# controller2.net
KiCad netlist of a schematic drawn in EAGLE
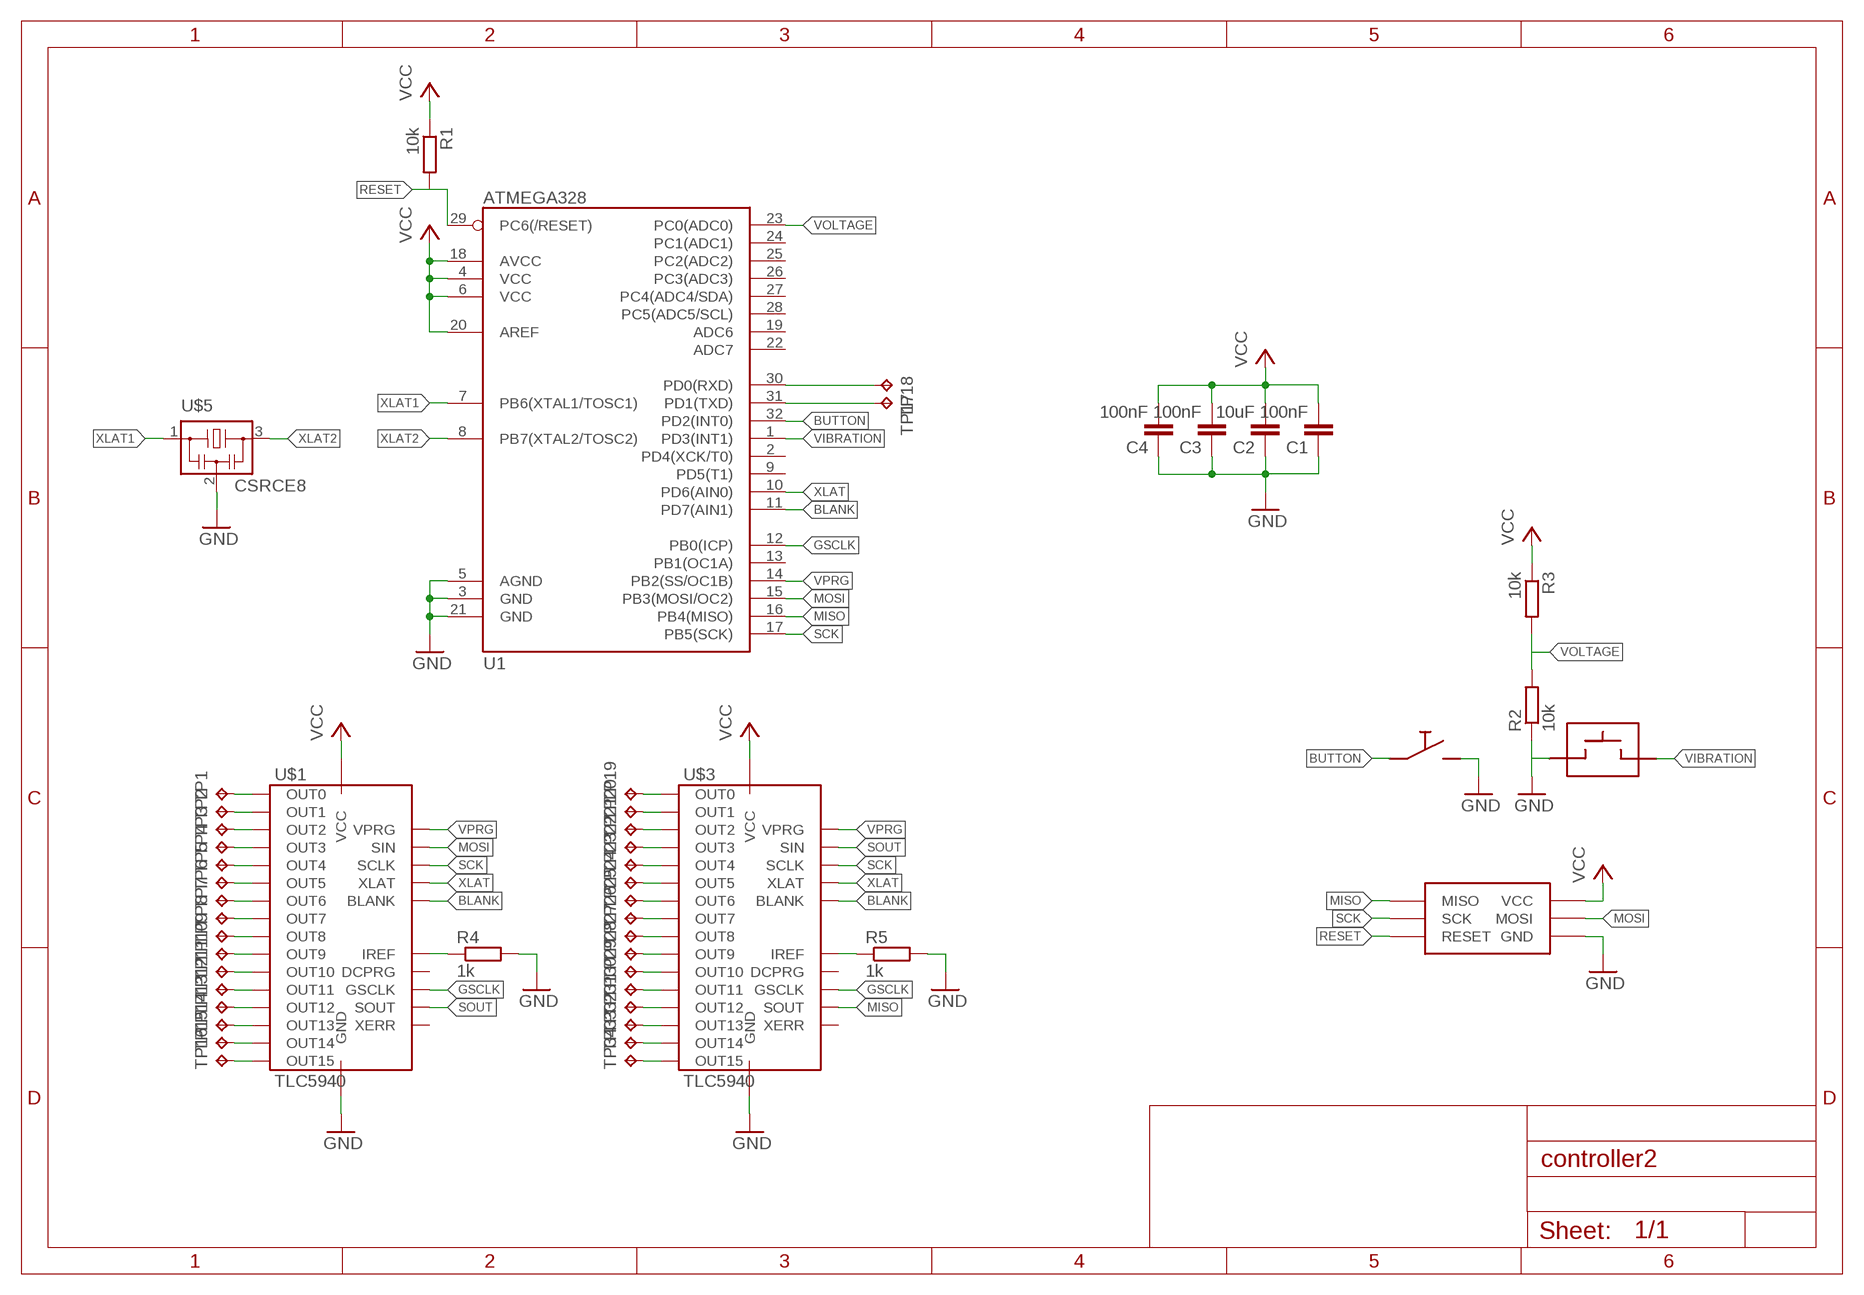
[diagram p0: schematic, sheet 1]

(export (version "E")
  (design (tool "Eeschema 10.0.6"))
  (components
    (comp (ref "C1")
      (value "100nF")
      (footprint "eagle-import:C0603")
      (libsource (lib "eagle-import") (part "C-EUC0603"))
    )
    (comp (ref "C2")
      (value "10uF")
      (footprint "eagle-import:C0805")
      (libsource (lib "eagle-import") (part "C-EUC0805"))
    )
    (comp (ref "C3")
      (value "100nF")
      (footprint "eagle-import:C0603")
      (libsource (lib "eagle-import") (part "C-EUC0603"))
    )
    (comp (ref "C4")
      (value "100nF")
      (footprint "eagle-import:C0603")
      (libsource (lib "eagle-import") (part "C-EUC0603"))
    )
    (comp (ref "R1")
      (value "10k")
      (footprint "eagle-import:R0603")
      (libsource (lib "eagle-import") (part "R-EU_R0603"))
    )
    (comp (ref "R2")
      (value "10k")
      (footprint "eagle-import:R0603")
      (libsource (lib "eagle-import") (part "R-EU_R0603"))
    )
    (comp (ref "R3")
      (value "10k")
      (footprint "eagle-import:R0603")
      (libsource (lib "eagle-import") (part "R-EU_R0603"))
    )
    (comp (ref "R4")
      (value "1k")
      (footprint "eagle-import:R0603")
      (libsource (lib "eagle-import") (part "R-EU_R0603"))
    )
    (comp (ref "R5")
      (value "1k")
      (footprint "eagle-import:R0603")
      (libsource (lib "eagle-import") (part "R-EU_R0603"))
    )
    (comp (ref "TP1")
      (value "TPTP15SQ")
      (footprint "eagle-import:TP15SQ")
      (libsource (lib "eagle-import") (part "TPTP15SQ"))
    )
    (comp (ref "TP2")
      (value "TPTP15SQ")
      (footprint "eagle-import:TP15SQ")
      (libsource (lib "eagle-import") (part "TPTP15SQ"))
    )
    (comp (ref "TP3")
      (value "TPTP15SQ")
      (footprint "eagle-import:TP15SQ")
      (libsource (lib "eagle-import") (part "TPTP15SQ"))
    )
    (comp (ref "TP4")
      (value "TPTP15SQ")
      (footprint "eagle-import:TP15SQ")
      (libsource (lib "eagle-import") (part "TPTP15SQ"))
    )
    (comp (ref "TP5")
      (value "TPTP15SQ")
      (footprint "eagle-import:TP15SQ")
      (libsource (lib "eagle-import") (part "TPTP15SQ"))
    )
    (comp (ref "TP6")
      (value "TPTP15SQ")
      (footprint "eagle-import:TP15SQ")
      (libsource (lib "eagle-import") (part "TPTP15SQ"))
    )
    (comp (ref "TP7")
      (value "TPTP15SQ")
      (footprint "eagle-import:TP15SQ")
      (libsource (lib "eagle-import") (part "TPTP15SQ"))
    )
    (comp (ref "TP8")
      (value "TPTP15SQ")
      (footprint "eagle-import:TP15SQ")
      (libsource (lib "eagle-import") (part "TPTP15SQ"))
    )
    (comp (ref "TP9")
      (value "TPTP15SQ")
      (footprint "eagle-import:TP15SQ")
      (libsource (lib "eagle-import") (part "TPTP15SQ"))
    )
    (comp (ref "TP10")
      (value "TPTP15SQ")
      (footprint "eagle-import:TP15SQ")
      (libsource (lib "eagle-import") (part "TPTP15SQ"))
    )
    (comp (ref "TP11")
      (value "TPTP15SQ")
      (footprint "eagle-import:TP15SQ")
      (libsource (lib "eagle-import") (part "TPTP15SQ"))
    )
    (comp (ref "TP12")
      (value "TPTP15SQ")
      (footprint "eagle-import:TP15SQ")
      (libsource (lib "eagle-import") (part "TPTP15SQ"))
    )
    (comp (ref "TP13")
      (value "TPTP15SQ")
      (footprint "eagle-import:TP15SQ")
      (libsource (lib "eagle-import") (part "TPTP15SQ"))
    )
    (comp (ref "TP14")
      (value "TPTP15SQ")
      (footprint "eagle-import:TP15SQ")
      (libsource (lib "eagle-import") (part "TPTP15SQ"))
    )
    (comp (ref "TP15")
      (value "TPTP15SQ")
      (footprint "eagle-import:TP15SQ")
      (libsource (lib "eagle-import") (part "TPTP15SQ"))
    )
    (comp (ref "TP16")
      (value "TPTP15SQ")
      (footprint "eagle-import:TP15SQ")
      (libsource (lib "eagle-import") (part "TPTP15SQ"))
    )
    (comp (ref "TP17")
      (value "TPTP15SQ")
      (footprint "eagle-import:TP15SQ")
      (libsource (lib "eagle-import") (part "TPTP15SQ"))
    )
    (comp (ref "TP18")
      (value "TPTP15SQ")
      (footprint "eagle-import:TP15SQ")
      (libsource (lib "eagle-import") (part "TPTP15SQ"))
    )
    (comp (ref "TP19")
      (value "TPTP15SQ")
      (footprint "eagle-import:TP15SQ")
      (libsource (lib "eagle-import") (part "TPTP15SQ"))
    )
    (comp (ref "TP20")
      (value "TPTP15SQ")
      (footprint "eagle-import:TP15SQ")
      (libsource (lib "eagle-import") (part "TPTP15SQ"))
    )
    (comp (ref "TP21")
      (value "TPTP15SQ")
      (footprint "eagle-import:TP15SQ")
      (libsource (lib "eagle-import") (part "TPTP15SQ"))
    )
    (comp (ref "TP22")
      (value "TPTP15SQ")
      (footprint "eagle-import:TP15SQ")
      (libsource (lib "eagle-import") (part "TPTP15SQ"))
    )
    (comp (ref "TP23")
      (value "TPTP15SQ")
      (footprint "eagle-import:TP15SQ")
      (libsource (lib "eagle-import") (part "TPTP15SQ"))
    )
    (comp (ref "TP24")
      (value "TPTP15SQ")
      (footprint "eagle-import:TP15SQ")
      (libsource (lib "eagle-import") (part "TPTP15SQ"))
    )
    (comp (ref "TP25")
      (value "TPTP15SQ")
      (footprint "eagle-import:TP15SQ")
      (libsource (lib "eagle-import") (part "TPTP15SQ"))
    )
    (comp (ref "TP26")
      (value "TPTP15SQ")
      (footprint "eagle-import:TP15SQ")
      (libsource (lib "eagle-import") (part "TPTP15SQ"))
    )
    (comp (ref "TP27")
      (value "TPTP15SQ")
      (footprint "eagle-import:TP15SQ")
      (libsource (lib "eagle-import") (part "TPTP15SQ"))
    )
    (comp (ref "TP28")
      (value "TPTP15SQ")
      (footprint "eagle-import:TP15SQ")
      (libsource (lib "eagle-import") (part "TPTP15SQ"))
    )
    (comp (ref "TP29")
      (value "TPTP15SQ")
      (footprint "eagle-import:TP15SQ")
      (libsource (lib "eagle-import") (part "TPTP15SQ"))
    )
    (comp (ref "TP30")
      (value "TPTP15SQ")
      (footprint "eagle-import:TP15SQ")
      (libsource (lib "eagle-import") (part "TPTP15SQ"))
    )
    (comp (ref "TP31")
      (value "TPTP15SQ")
      (footprint "eagle-import:TP15SQ")
      (libsource (lib "eagle-import") (part "TPTP15SQ"))
    )
    (comp (ref "TP32")
      (value "TPTP15SQ")
      (footprint "eagle-import:TP15SQ")
      (libsource (lib "eagle-import") (part "TPTP15SQ"))
    )
    (comp (ref "TP33")
      (value "TPTP15SQ")
      (footprint "eagle-import:TP15SQ")
      (libsource (lib "eagle-import") (part "TPTP15SQ"))
    )
    (comp (ref "TP34")
      (value "TPTP15SQ")
      (footprint "eagle-import:TP15SQ")
      (libsource (lib "eagle-import") (part "TPTP15SQ"))
    )
    (comp (ref "U$1")
      (value "TLC5940")
      (footprint "eagle-import:PWP_28PIN")
      (libsource (lib "eagle-import") (part "TLC5940"))
    )
    (comp (ref "U$2")
      (value "ISP_SPECIALS")
      (footprint "eagle-import:ISP_RM2_00_STRAIGHT")
      (libsource (lib "eagle-import") (part "ISP_SPECIALS"))
    )
    (comp (ref "U$3")
      (value "TLC5940")
      (footprint "eagle-import:PWP_28PIN")
      (libsource (lib "eagle-import") (part "TLC5940"))
    )
    (comp (ref "U$4")
      (value "MOTION_SENSOR")
      (footprint "eagle-import:MOTION")
      (libsource (lib "eagle-import") (part "MOTION_SENSOR"))
    )
    (comp (ref "U$5")
      (value "CSRCE8")
      (footprint "eagle-import:CSTCE_G")
      (libsource (lib "eagle-import") (part "CSRCE8"))
    )
    (comp (ref "U$6")
      (value "SWITCH")
      (footprint "eagle-import:EVQPSG02K")
      (libsource (lib "eagle-import") (part "SWITCH"))
    )
    (comp (ref "U1")
      (value "ATMEGA328")
      (footprint "eagle-import:TQFP32-08")
      (libsource (lib "eagle-import") (part "ATMEGA328"))
    )
  )
  (nets
    (net (code "1") (name "BLANK") (class "Default")
      (node (ref "U$1") (pin "P2") (pinfunction "BLANK_P2") (pintype "input"))
      (node (ref "U$3") (pin "P2") (pinfunction "BLANK_P2") (pintype "input"))
      (node (ref "U1") (pin "11") (pinfunction "PD7(AIN1)_11") (pintype "bidirectional"))
    )
    (net (code "2") (name "BUTTON") (class "Default")
      (node (ref "U$6") (pin "A") (pinfunction "P$1_A") (pintype "bidirectional"))
      (node (ref "U$6") (pin "A@2") (pinfunction "P$1_A@2") (pintype "bidirectional"))
      (node (ref "U1") (pin "32") (pinfunction "PD2(INT0)_32") (pintype "bidirectional"))
    )
    (net (code "3") (name "GND") (class "Default")
      (node (ref "C1") (pin "1") (pinfunction "1_1") (pintype "passive"))
      (node (ref "C2") (pin "1") (pinfunction "1_1") (pintype "passive"))
      (node (ref "C3") (pin "1") (pinfunction "1_1") (pintype "passive"))
      (node (ref "C4") (pin "1") (pinfunction "1_1") (pintype "passive"))
      (node (ref "R2") (pin "1") (pinfunction "1_1") (pintype "passive"))
      (node (ref "R4") (pin "2") (pinfunction "2_2") (pintype "passive"))
      (node (ref "R5") (pin "2") (pinfunction "2_2") (pintype "passive"))
      (node (ref "U$1") (pin "P1") (pinfunction "GND_P1") (pintype "power_in"))
      (node (ref "U$1") (pin "P29") (pinfunction "GND_P29") (pintype "power_in"))
      (node (ref "U$2") (pin "VCC") (pinfunction "GND_VCC") (pintype "bidirectional"))
      (node (ref "U$3") (pin "P1") (pinfunction "GND_P1") (pintype "power_in"))
      (node (ref "U$3") (pin "P29") (pinfunction "GND_P29") (pintype "power_in"))
      (node (ref "U$4") (pin "P$1") (pinfunction "IN_P$1") (pintype "bidirectional"))
      (node (ref "U$5") (pin "2") (pinfunction "2_2") (pintype "passive"))
      (node (ref "U$6") (pin "B") (pinfunction "P$2_B") (pintype "bidirectional"))
      (node (ref "U$6") (pin "B@2") (pinfunction "P$2_B@2") (pintype "bidirectional"))
      (node (ref "U1") (pin "21") (pinfunction "GND_21") (pintype "bidirectional"))
      (node (ref "U1") (pin "3") (pinfunction "GND_3") (pintype "bidirectional"))
      (node (ref "U1") (pin "5") (pinfunction "AGND_5") (pintype "bidirectional"))
    )
    (net (code "4") (name "GSCLK") (class "Default")
      (node (ref "U$1") (pin "P25") (pinfunction "GSCLK_P25") (pintype "input"))
      (node (ref "U$3") (pin "P25") (pinfunction "GSCLK_P25") (pintype "input"))
      (node (ref "U1") (pin "12") (pinfunction "PB0(ICP)_12") (pintype "bidirectional"))
    )
    (net (code "5") (name "MISO") (class "Default")
      (node (ref "U$2") (pin "RESET") (pinfunction "MISO_RESET") (pintype "bidirectional"))
      (node (ref "U$3") (pin "P24") (pinfunction "SOUT_P24") (pintype "output"))
      (node (ref "U1") (pin "16") (pinfunction "PB4(MISO)_16") (pintype "bidirectional"))
    )
    (net (code "6") (name "MOSI") (class "Default")
      (node (ref "U$1") (pin "P5") (pinfunction "SIN_P5") (pintype "input"))
      (node (ref "U$2") (pin "MOSI") (pinfunction "MOSI_MOSI") (pintype "bidirectional"))
      (node (ref "U1") (pin "15") (pinfunction "PB3(MOSI/OC2)_15") (pintype "bidirectional"))
    )
    (net (code "7") (name "Net-(U$1-IREF)") (class "Default")
      (node (ref "R4") (pin "1") (pinfunction "1_1") (pintype "passive"))
      (node (ref "U$1") (pin "P27") (pinfunction "IREF_P27") (pintype "passive"))
    )
    (net (code "8") (name "Net-(U$1-OUT0)") (class "Default")
      (node (ref "TP1") (pin "TP") (pinfunction "TP_TP") (pintype "input"))
      (node (ref "U$1") (pin "P7") (pinfunction "OUT0_P7") (pintype "open_collector"))
    )
    (net (code "9") (name "Net-(U$1-OUT1)") (class "Default")
      (node (ref "TP2") (pin "TP") (pinfunction "TP_TP") (pintype "input"))
      (node (ref "U$1") (pin "P8") (pinfunction "OUT1_P8") (pintype "open_collector"))
    )
    (net (code "10") (name "Net-(U$1-OUT2)") (class "Default")
      (node (ref "TP3") (pin "TP") (pinfunction "TP_TP") (pintype "input"))
      (node (ref "U$1") (pin "P9") (pinfunction "OUT2_P9") (pintype "open_collector"))
    )
    (net (code "11") (name "Net-(U$1-OUT3)") (class "Default")
      (node (ref "TP4") (pin "TP") (pinfunction "TP_TP") (pintype "input"))
      (node (ref "U$1") (pin "P10") (pinfunction "OUT3_P10") (pintype "open_collector"))
    )
    (net (code "12") (name "Net-(U$1-OUT4)") (class "Default")
      (node (ref "TP5") (pin "TP") (pinfunction "TP_TP") (pintype "input"))
      (node (ref "U$1") (pin "P11") (pinfunction "OUT4_P11") (pintype "open_collector"))
    )
    (net (code "13") (name "Net-(U$1-OUT5)") (class "Default")
      (node (ref "TP6") (pin "TP") (pinfunction "TP_TP") (pintype "input"))
      (node (ref "U$1") (pin "P12") (pinfunction "OUT5_P12") (pintype "open_collector"))
    )
    (net (code "14") (name "Net-(U$1-OUT6)") (class "Default")
      (node (ref "TP7") (pin "TP") (pinfunction "TP_TP") (pintype "input"))
      (node (ref "U$1") (pin "P13") (pinfunction "OUT6_P13") (pintype "open_collector"))
    )
    (net (code "15") (name "Net-(U$1-OUT7)") (class "Default")
      (node (ref "TP8") (pin "TP") (pinfunction "TP_TP") (pintype "input"))
      (node (ref "U$1") (pin "P14") (pinfunction "OUT7_P14") (pintype "open_collector"))
    )
    (net (code "16") (name "Net-(U$1-OUT8)") (class "Default")
      (node (ref "TP9") (pin "TP") (pinfunction "TP_TP") (pintype "input"))
      (node (ref "U$1") (pin "P15") (pinfunction "OUT8_P15") (pintype "open_collector"))
    )
    (net (code "17") (name "Net-(U$1-OUT9)") (class "Default")
      (node (ref "TP10") (pin "TP") (pinfunction "TP_TP") (pintype "input"))
      (node (ref "U$1") (pin "P16") (pinfunction "OUT9_P16") (pintype "open_collector"))
    )
    (net (code "18") (name "Net-(U$1-OUT10)") (class "Default")
      (node (ref "TP11") (pin "TP") (pinfunction "TP_TP") (pintype "input"))
      (node (ref "U$1") (pin "P17") (pinfunction "OUT10_P17") (pintype "open_collector"))
    )
    (net (code "19") (name "Net-(U$1-OUT11)") (class "Default")
      (node (ref "TP12") (pin "TP") (pinfunction "TP_TP") (pintype "input"))
      (node (ref "U$1") (pin "P18") (pinfunction "OUT11_P18") (pintype "open_collector"))
    )
    (net (code "20") (name "Net-(U$1-OUT12)") (class "Default")
      (node (ref "TP13") (pin "TP") (pinfunction "TP_TP") (pintype "input"))
      (node (ref "U$1") (pin "P19") (pinfunction "OUT12_P19") (pintype "open_collector"))
    )
    (net (code "21") (name "Net-(U$1-OUT13)") (class "Default")
      (node (ref "TP14") (pin "TP") (pinfunction "TP_TP") (pintype "input"))
      (node (ref "U$1") (pin "P20") (pinfunction "OUT13_P20") (pintype "open_collector"))
    )
    (net (code "22") (name "Net-(U$1-OUT14)") (class "Default")
      (node (ref "TP15") (pin "TP") (pinfunction "TP_TP") (pintype "input"))
      (node (ref "U$1") (pin "P21") (pinfunction "OUT14_P21") (pintype "open_collector"))
    )
    (net (code "23") (name "Net-(U$1-OUT15)") (class "Default")
      (node (ref "TP16") (pin "TP") (pinfunction "TP_TP") (pintype "input"))
      (node (ref "U$1") (pin "P22") (pinfunction "OUT15_P22") (pintype "open_collector"))
    )
    (net (code "24") (name "Net-(U$3-IREF)") (class "Default")
      (node (ref "R5") (pin "1") (pinfunction "1_1") (pintype "passive"))
      (node (ref "U$3") (pin "P27") (pinfunction "IREF_P27") (pintype "passive"))
    )
    (net (code "25") (name "Net-(U$3-OUT0)") (class "Default")
      (node (ref "TP19") (pin "TP") (pinfunction "TP_TP") (pintype "input"))
      (node (ref "U$3") (pin "P7") (pinfunction "OUT0_P7") (pintype "open_collector"))
    )
    (net (code "26") (name "Net-(U$3-OUT1)") (class "Default")
      (node (ref "TP20") (pin "TP") (pinfunction "TP_TP") (pintype "input"))
      (node (ref "U$3") (pin "P8") (pinfunction "OUT1_P8") (pintype "open_collector"))
    )
    (net (code "27") (name "Net-(U$3-OUT2)") (class "Default")
      (node (ref "TP21") (pin "TP") (pinfunction "TP_TP") (pintype "input"))
      (node (ref "U$3") (pin "P9") (pinfunction "OUT2_P9") (pintype "open_collector"))
    )
    (net (code "28") (name "Net-(U$3-OUT3)") (class "Default")
      (node (ref "TP22") (pin "TP") (pinfunction "TP_TP") (pintype "input"))
      (node (ref "U$3") (pin "P10") (pinfunction "OUT3_P10") (pintype "open_collector"))
    )
    (net (code "29") (name "Net-(U$3-OUT4)") (class "Default")
      (node (ref "TP23") (pin "TP") (pinfunction "TP_TP") (pintype "input"))
      (node (ref "U$3") (pin "P11") (pinfunction "OUT4_P11") (pintype "open_collector"))
    )
    (net (code "30") (name "Net-(U$3-OUT5)") (class "Default")
      (node (ref "TP24") (pin "TP") (pinfunction "TP_TP") (pintype "input"))
      (node (ref "U$3") (pin "P12") (pinfunction "OUT5_P12") (pintype "open_collector"))
    )
    (net (code "31") (name "Net-(U$3-OUT6)") (class "Default")
      (node (ref "TP25") (pin "TP") (pinfunction "TP_TP") (pintype "input"))
      (node (ref "U$3") (pin "P13") (pinfunction "OUT6_P13") (pintype "open_collector"))
    )
    (net (code "32") (name "Net-(U$3-OUT7)") (class "Default")
      (node (ref "TP26") (pin "TP") (pinfunction "TP_TP") (pintype "input"))
      (node (ref "U$3") (pin "P14") (pinfunction "OUT7_P14") (pintype "open_collector"))
    )
    (net (code "33") (name "Net-(U$3-OUT8)") (class "Default")
      (node (ref "TP27") (pin "TP") (pinfunction "TP_TP") (pintype "input"))
      (node (ref "U$3") (pin "P15") (pinfunction "OUT8_P15") (pintype "open_collector"))
    )
    (net (code "34") (name "Net-(U$3-OUT9)") (class "Default")
      (node (ref "TP28") (pin "TP") (pinfunction "TP_TP") (pintype "input"))
      (node (ref "U$3") (pin "P16") (pinfunction "OUT9_P16") (pintype "open_collector"))
    )
    (net (code "35") (name "Net-(U$3-OUT10)") (class "Default")
      (node (ref "TP29") (pin "TP") (pinfunction "TP_TP") (pintype "input"))
      (node (ref "U$3") (pin "P17") (pinfunction "OUT10_P17") (pintype "open_collector"))
    )
    (net (code "36") (name "Net-(U$3-OUT11)") (class "Default")
      (node (ref "TP30") (pin "TP") (pinfunction "TP_TP") (pintype "input"))
      (node (ref "U$3") (pin "P18") (pinfunction "OUT11_P18") (pintype "open_collector"))
    )
    (net (code "37") (name "Net-(U$3-OUT12)") (class "Default")
      (node (ref "TP31") (pin "TP") (pinfunction "TP_TP") (pintype "input"))
      (node (ref "U$3") (pin "P19") (pinfunction "OUT12_P19") (pintype "open_collector"))
    )
    (net (code "38") (name "Net-(U$3-OUT13)") (class "Default")
      (node (ref "TP32") (pin "TP") (pinfunction "TP_TP") (pintype "input"))
      (node (ref "U$3") (pin "P20") (pinfunction "OUT13_P20") (pintype "open_collector"))
    )
    (net (code "39") (name "Net-(U$3-OUT14)") (class "Default")
      (node (ref "TP33") (pin "TP") (pinfunction "TP_TP") (pintype "input"))
      (node (ref "U$3") (pin "P21") (pinfunction "OUT14_P21") (pintype "open_collector"))
    )
    (net (code "40") (name "Net-(U$3-OUT15)") (class "Default")
      (node (ref "TP34") (pin "TP") (pinfunction "TP_TP") (pintype "input"))
      (node (ref "U$3") (pin "P22") (pinfunction "OUT15_P22") (pintype "open_collector"))
    )
    (net (code "41") (name "Net-(U1-PD0(RXD))") (class "Default")
      (node (ref "TP18") (pin "TP") (pinfunction "TP_TP") (pintype "input"))
      (node (ref "U1") (pin "30") (pinfunction "PD0(RXD)_30") (pintype "bidirectional"))
    )
    (net (code "42") (name "Net-(U1-PD1(TXD))") (class "Default")
      (node (ref "TP17") (pin "TP") (pinfunction "TP_TP") (pintype "input"))
      (node (ref "U1") (pin "31") (pinfunction "PD1(TXD)_31") (pintype "bidirectional"))
    )
    (net (code "43") (name "RESET") (class "Default")
      (node (ref "R1") (pin "2") (pinfunction "2_2") (pintype "passive"))
      (node (ref "U$2") (pin "MISO") (pinfunction "RESET_MISO") (pintype "bidirectional"))
      (node (ref "U1") (pin "29") (pinfunction "PC6(/RESET)_29") (pintype "bidirectional"))
    )
    (net (code "44") (name "SCK") (class "Default")
      (node (ref "U$1") (pin "P4") (pinfunction "SCLK_P4") (pintype "input"))
      (node (ref "U$2") (pin "SCK") (pinfunction "SCK_SCK") (pintype "bidirectional"))
      (node (ref "U$3") (pin "P4") (pinfunction "SCLK_P4") (pintype "input"))
      (node (ref "U1") (pin "17") (pinfunction "PB5(SCK)_17") (pintype "bidirectional"))
    )
    (net (code "45") (name "SOUT") (class "Default")
      (node (ref "U$1") (pin "P24") (pinfunction "SOUT_P24") (pintype "output"))
      (node (ref "U$3") (pin "P5") (pinfunction "SIN_P5") (pintype "input"))
    )
    (net (code "46") (name "VCC") (class "Default")
      (node (ref "C1") (pin "2") (pinfunction "2_2") (pintype "passive"))
      (node (ref "C2") (pin "2") (pinfunction "2_2") (pintype "passive"))
      (node (ref "C3") (pin "2") (pinfunction "2_2") (pintype "passive"))
      (node (ref "C4") (pin "2") (pinfunction "2_2") (pintype "passive"))
      (node (ref "R1") (pin "1") (pinfunction "1_1") (pintype "passive"))
      (node (ref "R3") (pin "1") (pinfunction "1_1") (pintype "passive"))
      (node (ref "U$1") (pin "P28") (pinfunction "VCC_P28") (pintype "power_in"))
      (node (ref "U$2") (pin "GND") (pinfunction "VCC_GND") (pintype "bidirectional"))
      (node (ref "U$3") (pin "P28") (pinfunction "VCC_P28") (pintype "power_in"))
      (node (ref "U1") (pin "18") (pinfunction "AVCC_18") (pintype "bidirectional"))
      (node (ref "U1") (pin "20") (pinfunction "AREF_20") (pintype "bidirectional"))
      (node (ref "U1") (pin "4") (pinfunction "VCC_4") (pintype "bidirectional"))
      (node (ref "U1") (pin "6") (pinfunction "VCC_6") (pintype "bidirectional"))
    )
    (net (code "47") (name "VIBRATION") (class "Default")
      (node (ref "U$4") (pin "P$2") (pinfunction "OUT_P$2") (pintype "bidirectional"))
      (node (ref "U1") (pin "1") (pinfunction "PD3(INT1)_1") (pintype "bidirectional"))
    )
    (net (code "48") (name "VOLTAGE") (class "Default")
      (node (ref "R2") (pin "2") (pinfunction "2_2") (pintype "passive"))
      (node (ref "R3") (pin "2") (pinfunction "2_2") (pintype "passive"))
      (node (ref "U1") (pin "23") (pinfunction "PC0(ADC0)_23") (pintype "bidirectional"))
    )
    (net (code "49") (name "VPRG") (class "Default")
      (node (ref "U$1") (pin "P6") (pinfunction "VPRG_P6") (pintype "input"))
      (node (ref "U$3") (pin "P6") (pinfunction "VPRG_P6") (pintype "input"))
      (node (ref "U1") (pin "14") (pinfunction "PB2(SS/OC1B)_14") (pintype "bidirectional"))
    )
    (net (code "50") (name "XLAT") (class "Default")
      (node (ref "U$1") (pin "P3") (pinfunction "XLAT_P3") (pintype "input"))
      (node (ref "U$3") (pin "P3") (pinfunction "XLAT_P3") (pintype "input"))
      (node (ref "U1") (pin "10") (pinfunction "PD6(AIN0)_10") (pintype "bidirectional"))
    )
    (net (code "51") (name "XLAT1") (class "Default")
      (node (ref "U$5") (pin "1") (pinfunction "1_1") (pintype "passive"))
      (node (ref "U1") (pin "7") (pinfunction "PB6(XTAL1/TOSC1)_7") (pintype "bidirectional"))
    )
    (net (code "52") (name "XLAT2") (class "Default")
      (node (ref "U$5") (pin "3") (pinfunction "3_3") (pintype "passive"))
      (node (ref "U1") (pin "8") (pinfunction "PB7(XTAL2/TOSC2)_8") (pintype "bidirectional"))
    )
    (net (code "53") (name "unconnected-(U$1-DCPRG-PadP26)") (class "Default")
      (node (ref "U$1") (pin "P26") (pinfunction "DCPRG_P26") (pintype "input"))
    )
    (net (code "54") (name "unconnected-(U$1-XERR-PadP23)") (class "Default")
      (node (ref "U$1") (pin "P23") (pinfunction "XERR_P23") (pintype "open_collector"))
    )
    (net (code "55") (name "unconnected-(U$3-DCPRG-PadP26)") (class "Default")
      (node (ref "U$3") (pin "P26") (pinfunction "DCPRG_P26") (pintype "input"))
    )
    (net (code "56") (name "unconnected-(U$3-XERR-PadP23)") (class "Default")
      (node (ref "U$3") (pin "P23") (pinfunction "XERR_P23") (pintype "open_collector"))
    )
    (net (code "57") (name "unconnected-(U1-ADC6-Pad19)") (class "Default")
      (node (ref "U1") (pin "19") (pinfunction "ADC6_19") (pintype "bidirectional"))
    )
    (net (code "58") (name "unconnected-(U1-ADC7-Pad22)") (class "Default")
      (node (ref "U1") (pin "22") (pinfunction "ADC7_22") (pintype "bidirectional"))
    )
    (net (code "59") (name "unconnected-(U1-PB1(OC1A)-Pad13)") (class "Default")
      (node (ref "U1") (pin "13") (pinfunction "PB1(OC1A)_13") (pintype "bidirectional"))
    )
    (net (code "60") (name "unconnected-(U1-PC1(ADC1)-Pad24)") (class "Default")
      (node (ref "U1") (pin "24") (pinfunction "PC1(ADC1)_24") (pintype "bidirectional"))
    )
    (net (code "61") (name "unconnected-(U1-PC2(ADC2)-Pad25)") (class "Default")
      (node (ref "U1") (pin "25") (pinfunction "PC2(ADC2)_25") (pintype "bidirectional"))
    )
    (net (code "62") (name "unconnected-(U1-PC3(ADC3)-Pad26)") (class "Default")
      (node (ref "U1") (pin "26") (pinfunction "PC3(ADC3)_26") (pintype "bidirectional"))
    )
    (net (code "63") (name "unconnected-(U1-PC4(ADC4{slash}SDA)-Pad27)") (class "Default")
      (node (ref "U1") (pin "27") (pinfunction "PC4(ADC4/SDA)_27") (pintype "bidirectional"))
    )
    (net (code "64") (name "unconnected-(U1-PC5(ADC5{slash}SCL)-Pad28)") (class "Default")
      (node (ref "U1") (pin "28") (pinfunction "PC5(ADC5/SCL)_28") (pintype "bidirectional"))
    )
    (net (code "65") (name "unconnected-(U1-PD4(XCK{slash}T0)-Pad2)") (class "Default")
      (node (ref "U1") (pin "2") (pinfunction "PD4(XCK/T0)_2") (pintype "bidirectional"))
    )
    (net (code "66") (name "unconnected-(U1-PD5(T1)-Pad9)") (class "Default")
      (node (ref "U1") (pin "9") (pinfunction "PD5(T1)_9") (pintype "bidirectional"))
    )
  )
)
